# RoombaCatStalker.net
KiCad netlist of a schematic drawn in EAGLE
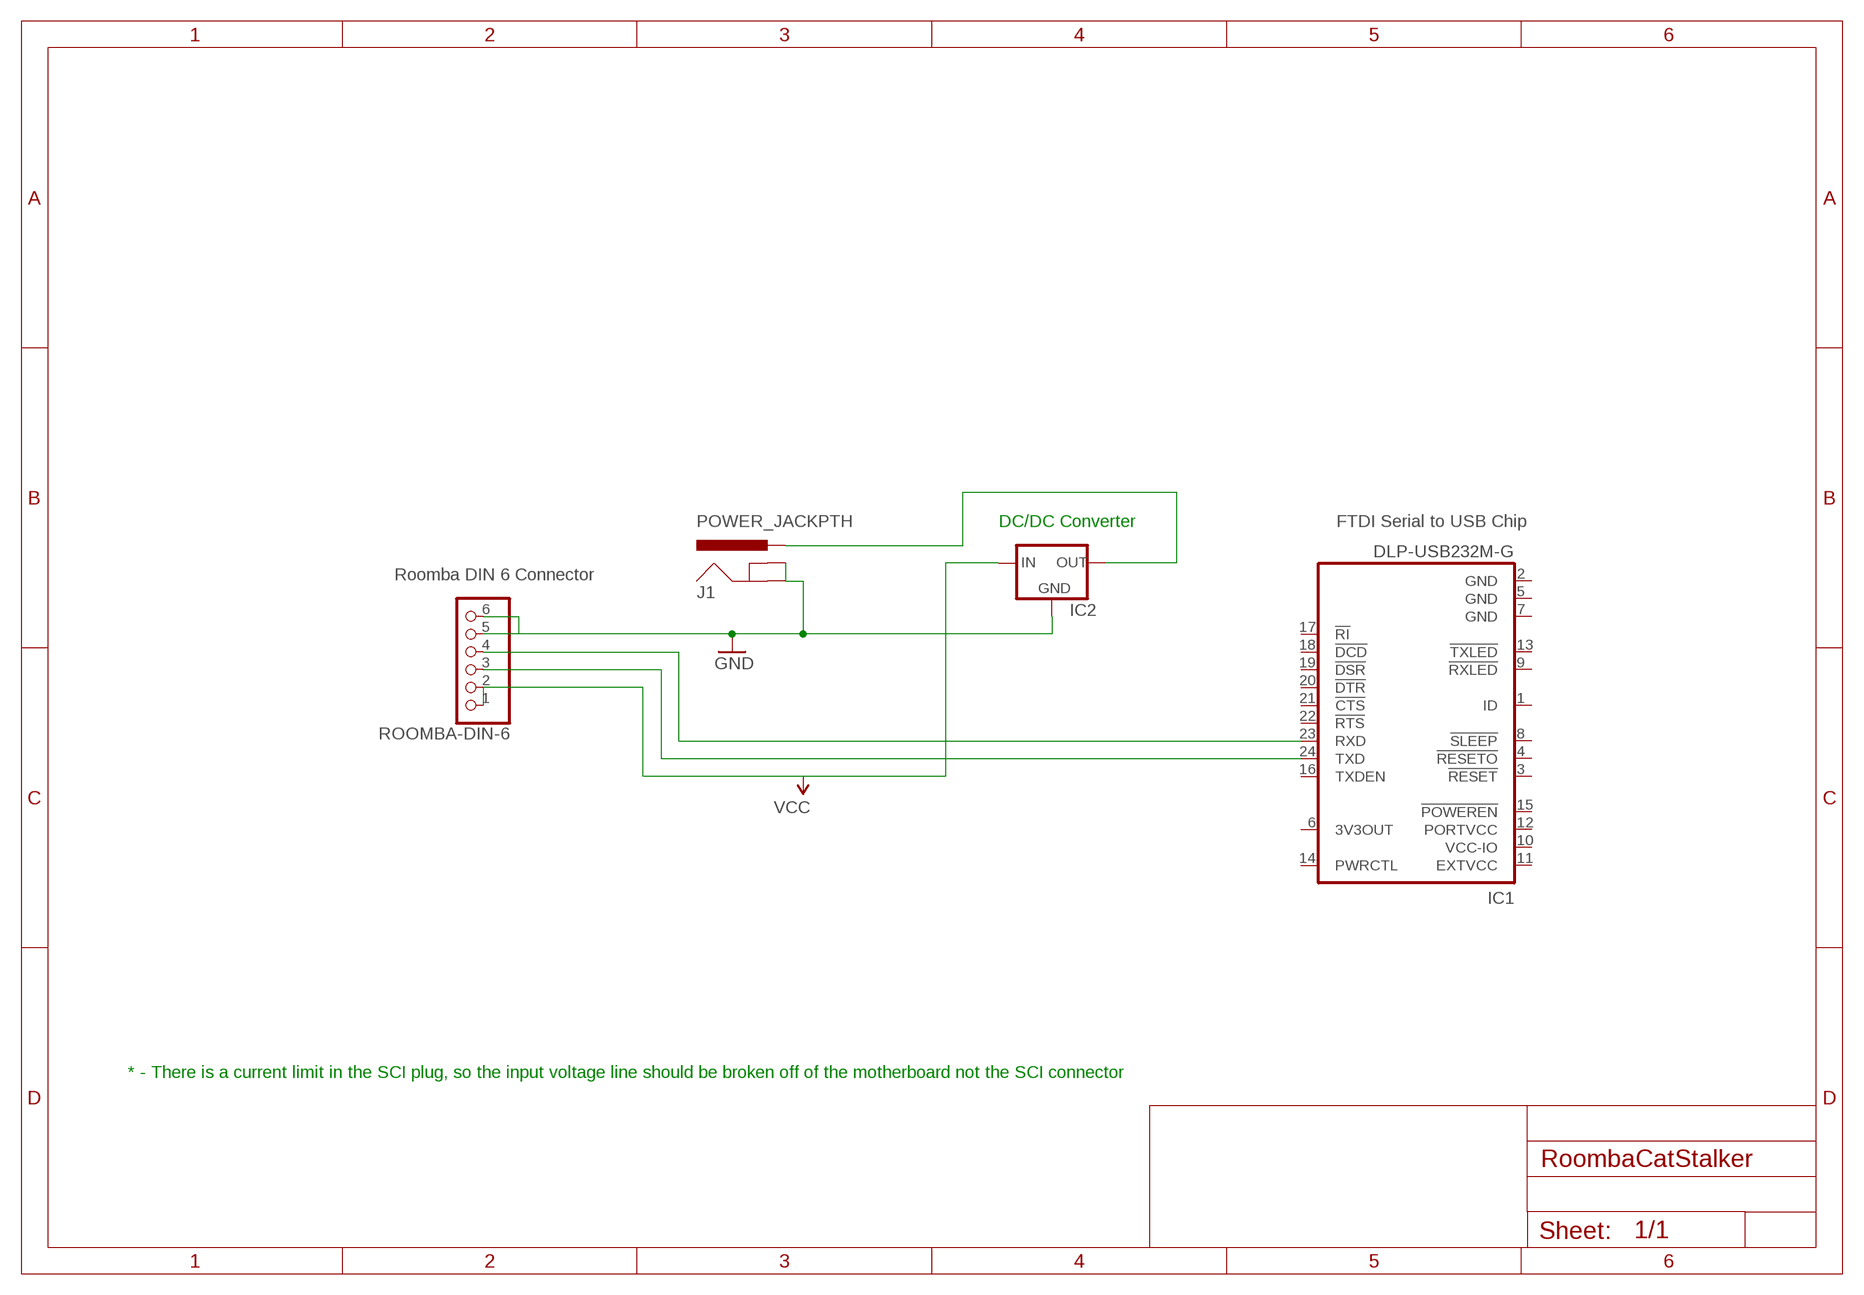
[diagram p0: schematic, sheet 1]

(export (version "E")
  (design (tool "Eeschema 10.0.6"))
  (components
    (comp (ref "IC1")
      (value "DLP-USB232M-G")
      (footprint "eagle-import:DLP-USB232M")
      (libsource (lib "eagle-import") (part "DLP-USB232M-G"))
    )
    (comp (ref "IC2")
      (value "XC63FPL")
      (footprint "eagle-import:TO92")
      (libsource (lib "eagle-import") (part "XC63FPL"))
    )
    (comp (ref "J1")
      (value "POWER_JACKPTH")
      (footprint "eagle-import:POWER_JACK_PTH")
      (libsource (lib "eagle-import") (part "POWER_JACKPTH"))
    )
    (comp (ref "ROOMBA-DIN-6")
      (value "PINHD-1X6")
      (footprint "eagle-import:1X06")
      (libsource (lib "eagle-import") (part "PINHD-1X6"))
    )
  )
  (nets
    (net (code "1") (name "GND") (class "Default")
      (node (ref "IC2") (pin "2") (pinfunction "GND_2") (pintype "input"))
      (node (ref "J1") (pin "GND") (pinfunction "GND_GND") (pintype "bidirectional"))
      (node (ref "J1") (pin "GNDBREAK") (pinfunction "GNDBREAK_GNDBREAK") (pintype "bidirectional"))
      (node (ref "ROOMBA-DIN-6") (pin "5") (pinfunction "5_5") (pintype "passive"))
      (node (ref "ROOMBA-DIN-6") (pin "6") (pinfunction "6_6") (pintype "passive"))
    )
    (net (code "2") (name "Net-(IC1-RXD)") (class "Default")
      (node (ref "IC1") (pin "23") (pinfunction "RXD_23") (pintype "input"))
      (node (ref "ROOMBA-DIN-6") (pin "4") (pinfunction "4_4") (pintype "passive"))
    )
    (net (code "3") (name "Net-(IC1-TXD)") (class "Default")
      (node (ref "IC1") (pin "24") (pinfunction "TXD_24") (pintype "input"))
      (node (ref "ROOMBA-DIN-6") (pin "3") (pinfunction "3_3") (pintype "passive"))
    )
    (net (code "4") (name "Net-(IC2-OUT)") (class "Default")
      (node (ref "IC2") (pin "3") (pinfunction "OUT_3") (pintype "passive"))
      (node (ref "J1") (pin "PWR") (pinfunction "PWR_PWR") (pintype "bidirectional"))
    )
    (net (code "5") (name "VCC") (class "Default")
      (node (ref "IC2") (pin "1") (pinfunction "IN_1") (pintype "input"))
      (node (ref "ROOMBA-DIN-6") (pin "1") (pinfunction "1_1") (pintype "passive"))
      (node (ref "ROOMBA-DIN-6") (pin "2") (pinfunction "2_2") (pintype "passive"))
    )
    (net (code "6") (name "unconnected-(IC1-3V3OUT-Pad6)") (class "Default")
      (node (ref "IC1") (pin "6") (pinfunction "3V3OUT_6") (pintype "input"))
    )
    (net (code "7") (name "unconnected-(IC1-EXTVCC-Pad11)") (class "Default")
      (node (ref "IC1") (pin "11") (pinfunction "EXTVCC_11") (pintype "input"))
    )
    (net (code "8") (name "unconnected-(IC1-GND-Pad2)") (class "Default")
      (node (ref "IC1") (pin "2") (pinfunction "GND_2") (pintype "input"))
    )
    (net (code "9") (name "unconnected-(IC1-GND-Pad5)") (class "Default")
      (node (ref "IC1") (pin "5") (pinfunction "GND_5") (pintype "input"))
    )
    (net (code "10") (name "unconnected-(IC1-GND-Pad7)") (class "Default")
      (node (ref "IC1") (pin "7") (pinfunction "GND_7") (pintype "input"))
    )
    (net (code "11") (name "unconnected-(IC1-ID-Pad1)") (class "Default")
      (node (ref "IC1") (pin "1") (pinfunction "ID_1") (pintype "input"))
    )
    (net (code "12") (name "unconnected-(IC1-PORTVCC-Pad12)") (class "Default")
      (node (ref "IC1") (pin "12") (pinfunction "PORTVCC_12") (pintype "input"))
    )
    (net (code "13") (name "unconnected-(IC1-PWRCTL-Pad14)") (class "Default")
      (node (ref "IC1") (pin "14") (pinfunction "PWRCTL_14") (pintype "input"))
    )
    (net (code "14") (name "unconnected-(IC1-TXDEN-Pad16)") (class "Default")
      (node (ref "IC1") (pin "16") (pinfunction "TXDEN_16") (pintype "input"))
    )
    (net (code "15") (name "unconnected-(IC1-VCC-IO-Pad10)") (class "Default")
      (node (ref "IC1") (pin "10") (pinfunction "VCC-IO_10") (pintype "input"))
    )
    (net (code "16") (name "unconnected-(IC1-~{CTS}-Pad21)") (class "Default")
      (node (ref "IC1") (pin "21") (pinfunction "~{CTS}_21") (pintype "input"))
    )
    (net (code "17") (name "unconnected-(IC1-~{DCD}-Pad18)") (class "Default")
      (node (ref "IC1") (pin "18") (pinfunction "~{DCD}_18") (pintype "input"))
    )
    (net (code "18") (name "unconnected-(IC1-~{DSR}-Pad19)") (class "Default")
      (node (ref "IC1") (pin "19") (pinfunction "~{DSR}_19") (pintype "input"))
    )
    (net (code "19") (name "unconnected-(IC1-~{DTR}-Pad20)") (class "Default")
      (node (ref "IC1") (pin "20") (pinfunction "~{DTR}_20") (pintype "input"))
    )
    (net (code "20") (name "unconnected-(IC1-~{POWEREN}-Pad15)") (class "Default")
      (node (ref "IC1") (pin "15") (pinfunction "~{POWEREN}_15") (pintype "input"))
    )
    (net (code "21") (name "unconnected-(IC1-~{RESETO}-Pad4)") (class "Default")
      (node (ref "IC1") (pin "4") (pinfunction "~{RESETO}_4") (pintype "input"))
    )
    (net (code "22") (name "unconnected-(IC1-~{RESET}-Pad3)") (class "Default")
      (node (ref "IC1") (pin "3") (pinfunction "~{RESET}_3") (pintype "input"))
    )
    (net (code "23") (name "unconnected-(IC1-~{RI}-Pad17)") (class "Default")
      (node (ref "IC1") (pin "17") (pinfunction "~{RI}_17") (pintype "input"))
    )
    (net (code "24") (name "unconnected-(IC1-~{RTS}-Pad22)") (class "Default")
      (node (ref "IC1") (pin "22") (pinfunction "~{RTS}_22") (pintype "input"))
    )
    (net (code "25") (name "unconnected-(IC1-~{RXLED}-Pad9)") (class "Default")
      (node (ref "IC1") (pin "9") (pinfunction "~{RXLED}_9") (pintype "input"))
    )
    (net (code "26") (name "unconnected-(IC1-~{SLEEP}-Pad8)") (class "Default")
      (node (ref "IC1") (pin "8") (pinfunction "~{SLEEP}_8") (pintype "input"))
    )
    (net (code "27") (name "unconnected-(IC1-~{TXLED}-Pad13)") (class "Default")
      (node (ref "IC1") (pin "13") (pinfunction "~{TXLED}_13") (pintype "input"))
    )
  )
)
